# 6-Latching_AMS.net
KiCad netlist of a schematic drawn in Altium Designer
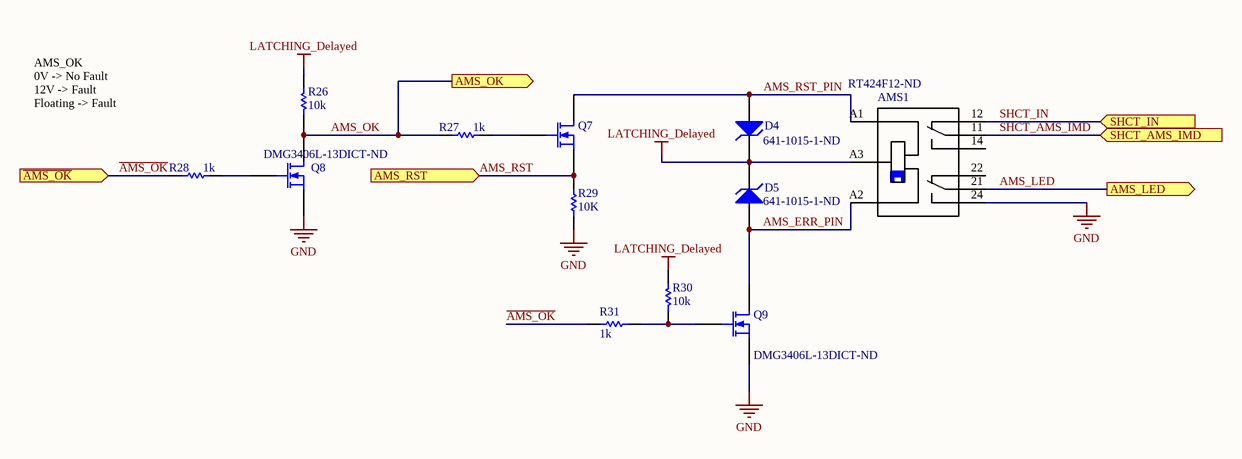
[diagram p0: 6-Latching AMS.SchDoc]

(export (version "E")
  (design (tool "Eeschema 10.0.6"))
  (components
    (comp (ref "AMS1")
      (value "5-1393243-4")
      (footprint "TE_5-1393243-4")
      (description "Electromechanical Relay 12VDC 240Ohm 15A DPDT __ 29mm 12.7mm 15.7mm__ THT Power Relay")
      (fields (field (name "MF") "TE Connectivity") (field (name "SUPPLIER PART NUMBER 1") "RT424F12-ND"))
      (libsource (lib "5-1393243-4") (part "5-1393243-4"))
    )
    (comp (ref "D4")
      (value "D Zener")
      (footprint "DO214AC")
      (description "Zener Diode")
      (fields
        (field (name "SUPPLIER PART NUMBER 1") "641-1015-1-ND")
        (field (name "PUBLISHER") "Altium Limited")
      )
      (libsource (lib "Miscellaneous Devices") (part "D Zener"))
    )
    (comp (ref "D5")
      (value "D Zener")
      (footprint "DO214AC")
      (description "Zener Diode")
      (fields
        (field (name "SUPPLIER PART NUMBER 1") "641-1015-1-ND")
        (field (name "PUBLISHER") "Altium Limited")
      )
      (libsource (lib "Miscellaneous Devices") (part "D Zener"))
    )
    (comp (ref "Q7")
      (value "~")
      (footprint "SOT-23_N")
      (description "N-Channel MOSFET")
      (fields
        (field (name "MANUFACTURER") "Infineon Technologies")
        (field (name "PUBLISHER") "Altium Limited")
      )
      (libsource (lib "Miscellaneous Devices") (part "MOSFET-N"))
    )
    (comp (ref "Q8")
      (value "~")
      (footprint "SOT-23_N")
      (description "N-Channel MOSFET")
      (fields
        (field (name "MANUFACTURER") "Infineon Technologies")
        (field (name "SUPPLIER PART NUMBER 1") "DMG3406L-13DICT-ND")
        (field (name "PUBLISHER") "Altium Limited")
      )
      (libsource (lib "Miscellaneous Devices") (part "MOSFET-N"))
    )
    (comp (ref "Q9")
      (value "~")
      (footprint "SOT-23_N")
      (description "N-Channel MOSFET")
      (fields
        (field (name "MANUFACTURER") "Infineon Technologies")
        (field (name "SUPPLIER PART NUMBER 1") "DMG3406L-13DICT-ND")
        (field (name "PUBLISHER") "Altium Limited")
      )
      (libsource (lib "Miscellaneous Devices") (part "MOSFET-N"))
    )
    (comp (ref "R26")
      (value "RHM1.0KDCT-ND")
      (footprint "1608[0603]")
      (description "RES SMD 1.0K OHM 5% 1/4W 0603")
      (fields
        (field (name "MANUFACTURER") "Rohm Semiconductor")
        (field (name "MANUFACTURER PART NUMBER") "ESR03EZPJ102")
        (field (name "RESISTANCE (OHMS)") "10k")
      )
      (libsource (lib "Miscellaneous Devices") (part "Res1"))
    )
    (comp (ref "R27")
      (value "1k")
      (footprint "1608[0603]")
      (description "RES SMD 100 OHM 5% 1/4W 0603")
      (fields
        (field (name "MANUFACTURER") "Rohm Semiconductor")
        (field (name "MANUFACTURER PART NUMBER") "ESR03EZPJ101")
        (field (name "PUBLISHER") "Altium Limited")
      )
      (libsource (lib "Miscellaneous Devices") (part "Res1"))
    )
    (comp (ref "R28")
      (value "1k")
      (footprint "1608[0603]")
      (description "RES SMD 100 OHM 5% 1/4W 0603")
      (fields
        (field (name "MANUFACTURER") "Rohm Semiconductor")
        (field (name "MANUFACTURER PART NUMBER") "ESR03EZPJ101")
        (field (name "PUBLISHER") "Altium Limited")
      )
      (libsource (lib "Miscellaneous Devices") (part "Res1"))
    )
    (comp (ref "R29")
      (value "10K")
      (footprint "1608[0603]")
      (description "RES SMD 10K OHM 5% 1/4W 0603")
      (fields
        (field (name "MANUFACTURER") "Rohm Semiconductor")
        (field (name "MANUFACTURER PART NUMBER") "ESR03EZPJ103")
        (field (name "PUBLISHER") "Altium Limited")
      )
      (libsource (lib "Miscellaneous Devices") (part "Res1"))
    )
    (comp (ref "R30")
      (value "RHM1.0KDCT-ND")
      (footprint "1608[0603]")
      (description "RES SMD 1.0K OHM 5% 1/4W 0603")
      (fields
        (field (name "MANUFACTURER") "Rohm Semiconductor")
        (field (name "MANUFACTURER PART NUMBER") "ESR03EZPJ102")
        (field (name "RESISTANCE (OHMS)") "10k")
      )
      (libsource (lib "Miscellaneous Devices") (part "Res1"))
    )
    (comp (ref "R31")
      (value "1k")
      (footprint "1608[0603]")
      (description "Resistor")
      (fields
        (field (name "MANUFACTURER") "Panasonic Electronic Components")
        (field (name "MANUFACTURER PART NUMBER") "ERJ-3EKF60R4V")
        (field (name "PUBLISHER") "Altium Limited")
      )
      (libsource (lib "Miscellaneous Devices") (part "Res1"))
    )
  )
  (nets
    (net (code "1") (name "/AMS_ERR_PIN") (class "Default")
      (node (ref "AMS1") (pin "A2") (pinfunction "A2_A2") (pintype "passive"))
      (node (ref "D5") (pin "1") (pinfunction "A_1") (pintype "passive"))
      (node (ref "Q9") (pin "3") (pinfunction "D_3") (pintype "passive"))
    )
    (net (code "2") (name "/AMS_LED") (class "Default")
      (node (ref "AMS1") (pin "21") (pinfunction "21_21") (pintype "passive"))
    )
    (net (code "3") (name "/AMS_OK") (class "Default")
      (node (ref "Q8") (pin "3") (pinfunction "D_3") (pintype "passive"))
      (node (ref "R26") (pin "2") (pinfunction "2_2") (pintype "passive"))
      (node (ref "R27") (pin "1") (pinfunction "1_1") (pintype "passive"))
    )
    (net (code "4") (name "/AMS_RST") (class "Default")
      (node (ref "Q7") (pin "2") (pinfunction "S_2") (pintype "passive"))
      (node (ref "R29") (pin "2") (pinfunction "2_2") (pintype "passive"))
    )
    (net (code "5") (name "/AMS_RST_PIN") (class "Default")
      (node (ref "AMS1") (pin "A1") (pinfunction "A1_A1") (pintype "passive"))
      (node (ref "D4") (pin "1") (pinfunction "A_1") (pintype "passive"))
      (node (ref "Q7") (pin "3") (pinfunction "D_3") (pintype "passive"))
    )
    (net (code "6") (name "/SHCT_AMS_IMD") (class "Default")
      (node (ref "AMS1") (pin "11") (pinfunction "11_11") (pintype "passive"))
    )
    (net (code "7") (name "/SHCT_IN") (class "Default")
      (node (ref "AMS1") (pin "12") (pinfunction "12_12") (pintype "passive"))
    )
    (net (code "8") (name "/~{AMS_OK}") (class "Default")
      (node (ref "R28") (pin "1") (pinfunction "1_1") (pintype "passive"))
      (node (ref "R31") (pin "1") (pinfunction "1_1") (pintype "passive"))
    )
    (net (code "9") (name "GND") (class "Default")
      (node (ref "AMS1") (pin "24") (pinfunction "24_24") (pintype "passive"))
      (node (ref "Q8") (pin "2") (pinfunction "S_2") (pintype "passive"))
      (node (ref "Q9") (pin "2") (pinfunction "S_2") (pintype "passive"))
      (node (ref "R29") (pin "1") (pinfunction "1_1") (pintype "passive"))
    )
    (net (code "10") (name "LATCHING_Delayed") (class "Default")
      (node (ref "AMS1") (pin "A3") (pinfunction "A3_A3") (pintype "passive"))
      (node (ref "D4") (pin "2") (pinfunction "K_2") (pintype "passive"))
      (node (ref "D5") (pin "2") (pinfunction "K_2") (pintype "passive"))
      (node (ref "R26") (pin "1") (pinfunction "1_1") (pintype "passive"))
      (node (ref "R30") (pin "1") (pinfunction "1_1") (pintype "passive"))
    )
    (net (code "11") (name "Net-(Q7-G)") (class "Default")
      (node (ref "Q7") (pin "1") (pinfunction "G_1") (pintype "passive"))
      (node (ref "R27") (pin "2") (pinfunction "2_2") (pintype "passive"))
    )
    (net (code "12") (name "Net-(Q8-G)") (class "Default")
      (node (ref "Q8") (pin "1") (pinfunction "G_1") (pintype "passive"))
      (node (ref "R28") (pin "2") (pinfunction "2_2") (pintype "passive"))
    )
    (net (code "13") (name "Net-(Q9-G)") (class "Default")
      (node (ref "Q9") (pin "1") (pinfunction "G_1") (pintype "passive"))
      (node (ref "R30") (pin "2") (pinfunction "2_2") (pintype "passive"))
      (node (ref "R31") (pin "2") (pinfunction "2_2") (pintype "passive"))
    )
    (net (code "14") (name "unconnected-(AMS1-Pad14)") (class "Default")
      (node (ref "AMS1") (pin "14") (pinfunction "14_14") (pintype "passive"))
    )
    (net (code "15") (name "unconnected-(AMS1-Pad22)") (class "Default")
      (node (ref "AMS1") (pin "22") (pinfunction "22_22") (pintype "passive"))
    )
  )
)
